# dxlboard.net
KiCad netlist of a schematic drawn in EAGLE
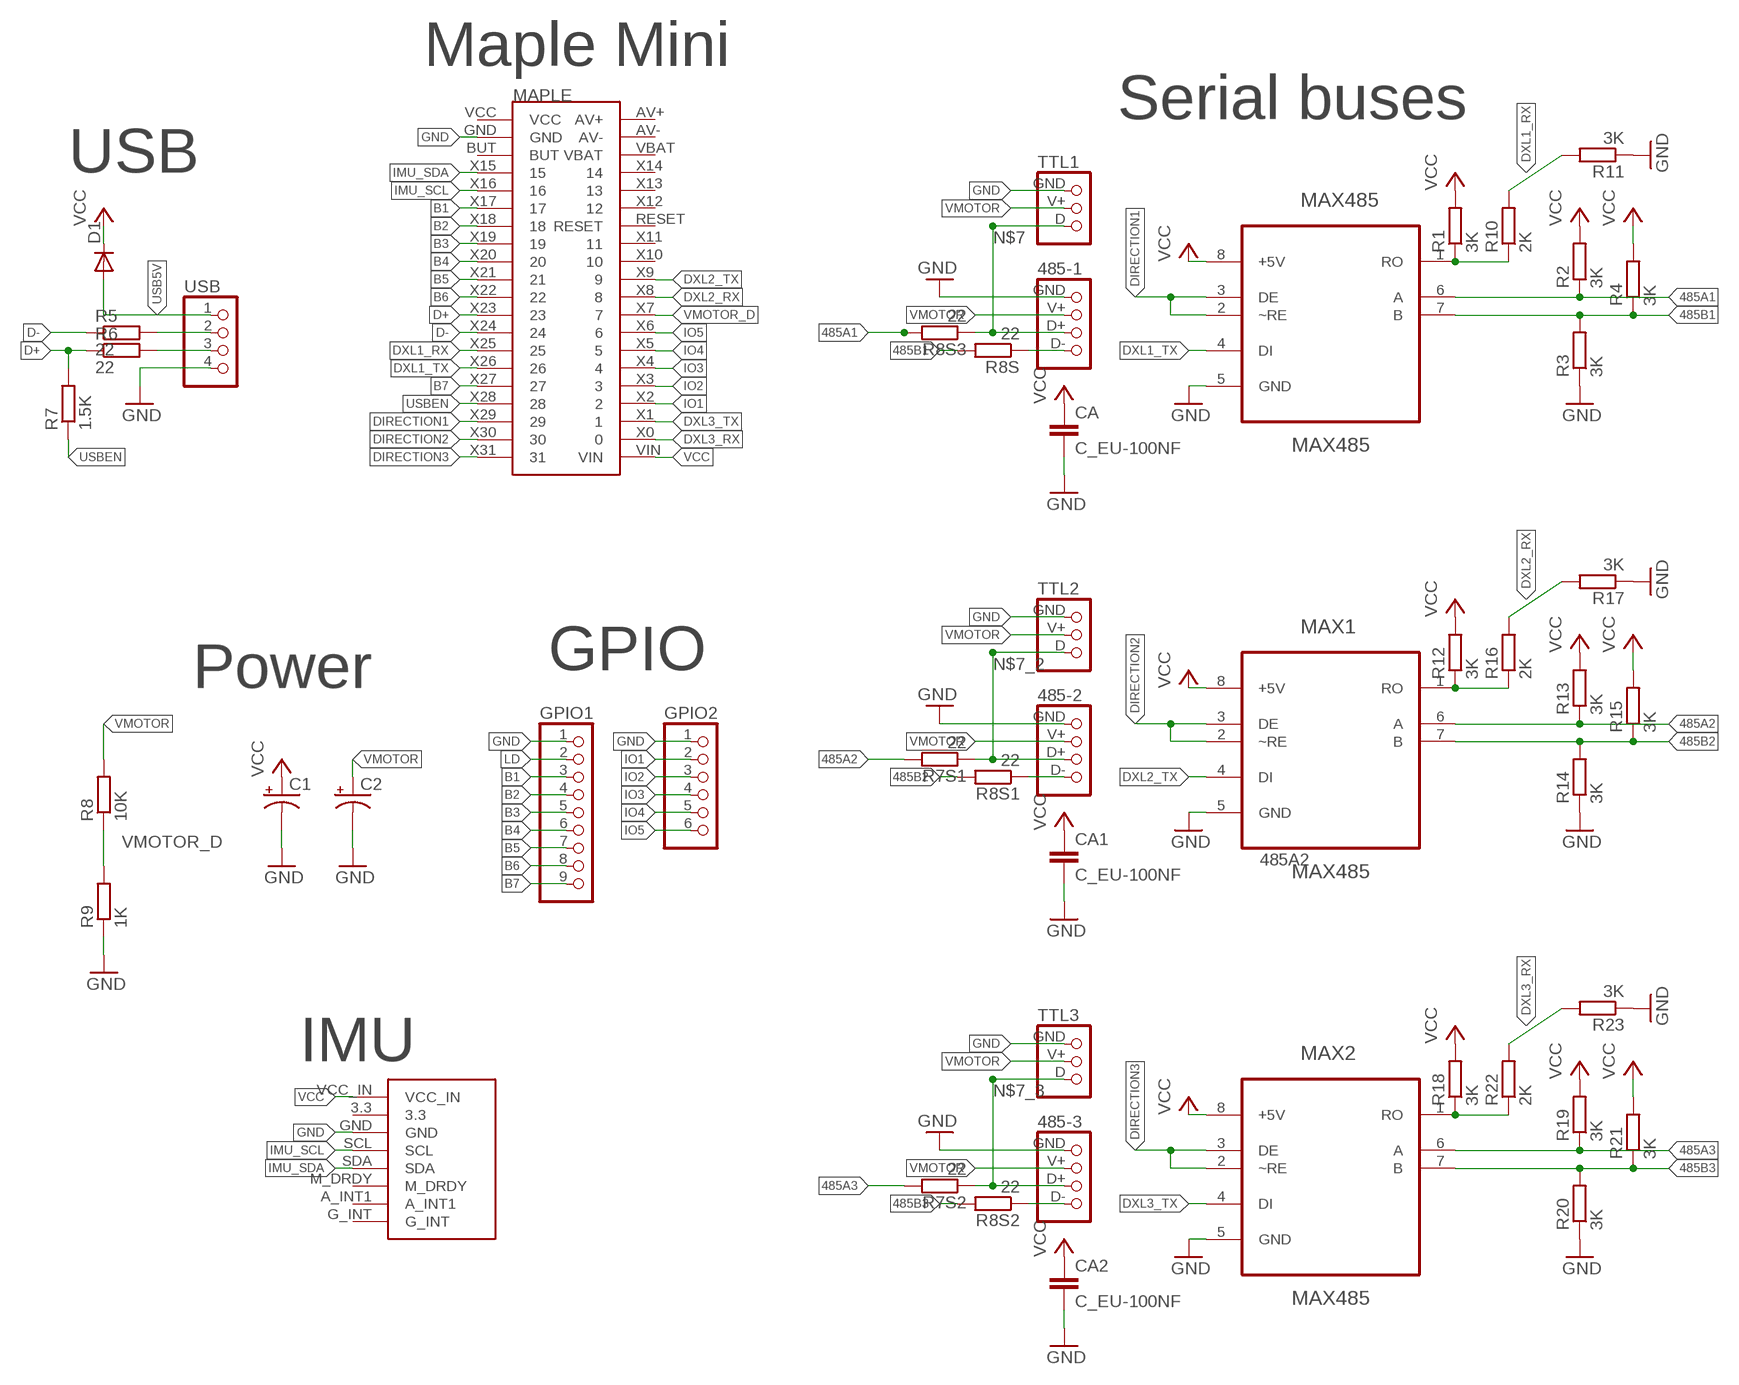
[diagram p0: schematic, sheet 1]

(export (version "E")
  (design (tool "Eeschema 10.0.6"))
  (components
    (comp (ref "485-1")
      (value "CONNEC_1X04_485")
      (footprint "eagle-import:CONNEC_485")
      (libsource (lib "eagle-import") (part "CONNEC_1X04_485"))
    )
    (comp (ref "485-2")
      (value "CONNEC_1X04_485")
      (footprint "eagle-import:CONNEC_485")
      (libsource (lib "eagle-import") (part "CONNEC_1X04_485"))
    )
    (comp (ref "485-3")
      (value "CONNEC_1X04_485")
      (footprint "eagle-import:CONNEC_485")
      (libsource (lib "eagle-import") (part "CONNEC_1X04_485"))
    )
    (comp (ref "C1")
      (value "CAP_POLPTH2")
      (footprint "eagle-import:CPOL-RADIAL-10UF-25V")
      (libsource (lib "eagle-import") (part "CAP_POLPTH2"))
    )
    (comp (ref "C2")
      (value "CAP_POLPTH2")
      (footprint "eagle-import:CPOL-RADIAL-10UF-25V")
      (libsource (lib "eagle-import") (part "CAP_POLPTH2"))
    )
    (comp (ref "CA")
      (value "C_EU-100NF")
      (footprint "eagle-import:C0805")
      (libsource (lib "eagle-import") (part "C_EU-100NF"))
    )
    (comp (ref "CA1")
      (value "C_EU-100NF")
      (footprint "eagle-import:C0805")
      (libsource (lib "eagle-import") (part "C_EU-100NF"))
    )
    (comp (ref "CA2")
      (value "C_EU-100NF")
      (footprint "eagle-import:C0805")
      (libsource (lib "eagle-import") (part "C_EU-100NF"))
    )
    (comp (ref "D1")
      (value "DIODESOD")
      (footprint "eagle-import:SOD-323")
      (libsource (lib "eagle-import") (part "DIODESOD"))
    )
    (comp (ref "GPIO1")
      (value "CONNEC_1X09")
      (footprint "eagle-import:CONNEC_1X09")
      (libsource (lib "eagle-import") (part "CONNEC_1X09"))
    )
    (comp (ref "GPIO2")
      (value "CONNEC_1X06")
      (footprint "eagle-import:CONNEC_1X06")
      (libsource (lib "eagle-import") (part "CONNEC_1X06"))
    )
    (comp (ref "MAPLE")
      (value "MAPLE_MINI")
      (footprint "eagle-import:CONNEC_2X20")
      (libsource (lib "eagle-import") (part "MAPLE_MINI"))
    )
    (comp (ref "MAX1")
      (value "MAX485")
      (footprint "eagle-import:SO8")
      (fields (field (name "MPN") "MAX485EESA+"))
      (libsource (lib "eagle-import") (part "MAX485"))
    )
    (comp (ref "MAX2")
      (value "MAX485")
      (footprint "eagle-import:SO8")
      (fields (field (name "MPN") "MAX485EESA+"))
      (libsource (lib "eagle-import") (part "MAX485"))
    )
    (comp (ref "MAX485")
      (value "MAX485")
      (footprint "eagle-import:SO8")
      (fields (field (name "MPN") "MAX485EESA+"))
      (libsource (lib "eagle-import") (part "MAX485"))
    )
    (comp (ref "R1")
      (value "3K")
      (footprint "eagle-import:R0805")
      (libsource (lib "eagle-import") (part "RESISTANCE-R0805"))
    )
    (comp (ref "R2")
      (value "3K")
      (footprint "eagle-import:R0805")
      (libsource (lib "eagle-import") (part "RESISTANCE-R0805"))
    )
    (comp (ref "R3")
      (value "3K")
      (footprint "eagle-import:R0805")
      (libsource (lib "eagle-import") (part "RESISTANCE-R0805"))
    )
    (comp (ref "R4")
      (value "3K")
      (footprint "eagle-import:R0805")
      (libsource (lib "eagle-import") (part "RESISTANCE-R0805"))
    )
    (comp (ref "R5")
      (value "22")
      (footprint "eagle-import:R0805")
      (libsource (lib "eagle-import") (part "RESISTANCE-R0805"))
    )
    (comp (ref "R6")
      (value "22")
      (footprint "eagle-import:R0805")
      (libsource (lib "eagle-import") (part "RESISTANCE-R0805"))
    )
    (comp (ref "R7")
      (value "1.5K")
      (footprint "eagle-import:R0805")
      (libsource (lib "eagle-import") (part "RESISTANCE-R0805"))
    )
    (comp (ref "R7S1")
      (value "22")
      (footprint "eagle-import:R0805")
      (libsource (lib "eagle-import") (part "RESISTANCE-R0805"))
    )
    (comp (ref "R7S2")
      (value "22")
      (footprint "eagle-import:R0805")
      (libsource (lib "eagle-import") (part "RESISTANCE-R0805"))
    )
    (comp (ref "R8")
      (value "10K")
      (footprint "eagle-import:R0805")
      (libsource (lib "eagle-import") (part "RESISTANCE-R0805"))
    )
    (comp (ref "R8S")
      (value "22")
      (footprint "eagle-import:R0805")
      (libsource (lib "eagle-import") (part "RESISTANCE-R0805"))
    )
    (comp (ref "R8S1")
      (value "22")
      (footprint "eagle-import:R0805")
      (libsource (lib "eagle-import") (part "RESISTANCE-R0805"))
    )
    (comp (ref "R8S2")
      (value "22")
      (footprint "eagle-import:R0805")
      (libsource (lib "eagle-import") (part "RESISTANCE-R0805"))
    )
    (comp (ref "R8S3")
      (value "22")
      (footprint "eagle-import:R0805")
      (libsource (lib "eagle-import") (part "RESISTANCE-R0805"))
    )
    (comp (ref "R9")
      (value "1K")
      (footprint "eagle-import:R0805")
      (libsource (lib "eagle-import") (part "RESISTANCE-R0805"))
    )
    (comp (ref "R10")
      (value "2K")
      (footprint "eagle-import:R0805")
      (libsource (lib "eagle-import") (part "RESISTANCE-R0805"))
    )
    (comp (ref "R11")
      (value "3K")
      (footprint "eagle-import:R0805")
      (libsource (lib "eagle-import") (part "RESISTANCE-R0805"))
    )
    (comp (ref "R12")
      (value "3K")
      (footprint "eagle-import:R0805")
      (libsource (lib "eagle-import") (part "RESISTANCE-R0805"))
    )
    (comp (ref "R13")
      (value "3K")
      (footprint "eagle-import:R0805")
      (libsource (lib "eagle-import") (part "RESISTANCE-R0805"))
    )
    (comp (ref "R14")
      (value "3K")
      (footprint "eagle-import:R0805")
      (libsource (lib "eagle-import") (part "RESISTANCE-R0805"))
    )
    (comp (ref "R15")
      (value "3K")
      (footprint "eagle-import:R0805")
      (libsource (lib "eagle-import") (part "RESISTANCE-R0805"))
    )
    (comp (ref "R16")
      (value "2K")
      (footprint "eagle-import:R0805")
      (libsource (lib "eagle-import") (part "RESISTANCE-R0805"))
    )
    (comp (ref "R17")
      (value "3K")
      (footprint "eagle-import:R0805")
      (libsource (lib "eagle-import") (part "RESISTANCE-R0805"))
    )
    (comp (ref "R18")
      (value "3K")
      (footprint "eagle-import:R0805")
      (libsource (lib "eagle-import") (part "RESISTANCE-R0805"))
    )
    (comp (ref "R19")
      (value "3K")
      (footprint "eagle-import:R0805")
      (libsource (lib "eagle-import") (part "RESISTANCE-R0805"))
    )
    (comp (ref "R20")
      (value "3K")
      (footprint "eagle-import:R0805")
      (libsource (lib "eagle-import") (part "RESISTANCE-R0805"))
    )
    (comp (ref "R21")
      (value "3K")
      (footprint "eagle-import:R0805")
      (libsource (lib "eagle-import") (part "RESISTANCE-R0805"))
    )
    (comp (ref "R22")
      (value "2K")
      (footprint "eagle-import:R0805")
      (libsource (lib "eagle-import") (part "RESISTANCE-R0805"))
    )
    (comp (ref "R23")
      (value "3K")
      (footprint "eagle-import:R0805")
      (libsource (lib "eagle-import") (part "RESISTANCE-R0805"))
    )
    (comp (ref "TTL1")
      (value "CONNEC_1X03_TTL")
      (footprint "eagle-import:CONNEC_TTL")
      (libsource (lib "eagle-import") (part "CONNEC_1X03_TTL"))
    )
    (comp (ref "TTL2")
      (value "CONNEC_1X03_TTL")
      (footprint "eagle-import:CONNEC_TTL")
      (libsource (lib "eagle-import") (part "CONNEC_1X03_TTL"))
    )
    (comp (ref "TTL3")
      (value "CONNEC_1X03_TTL")
      (footprint "eagle-import:CONNEC_TTL")
      (libsource (lib "eagle-import") (part "CONNEC_1X03_TTL"))
    )
    (comp (ref "U$6")
      (value "GY-85")
      (footprint "eagle-import:GY-85")
      (libsource (lib "eagle-import") (part "GY-85"))
    )
    (comp (ref "USB")
      (value "CONNEC_1X04")
      (footprint "eagle-import:CONNEC_1X04")
      (libsource (lib "eagle-import") (part "CONNEC_1X04"))
    )
  )
  (nets
    (net (code "1") (name "/N$7") (class "Default")
      (node (ref "485-1") (pin "D+") (pinfunction "3_D+") (pintype "passive"))
      (node (ref "R8S3") (pin "1") (pinfunction "1_1") (pintype "passive"))
      (node (ref "TTL1") (pin "D") (pinfunction "3_D") (pintype "passive"))
    )
    (net (code "2") (name "/N$7_2") (class "Default")
      (node (ref "485-2") (pin "D+") (pinfunction "3_D+") (pintype "passive"))
      (node (ref "R7S1") (pin "1") (pinfunction "1_1") (pintype "passive"))
      (node (ref "TTL2") (pin "D") (pinfunction "3_D") (pintype "passive"))
    )
    (net (code "3") (name "/N$7_3") (class "Default")
      (node (ref "485-3") (pin "D+") (pinfunction "3_D+") (pintype "passive"))
      (node (ref "R7S2") (pin "1") (pinfunction "1_1") (pintype "passive"))
      (node (ref "TTL3") (pin "D") (pinfunction "3_D") (pintype "passive"))
    )
    (net (code "4") (name "485A1") (class "Default")
      (node (ref "MAX485") (pin "6") (pinfunction "A_6") (pintype "bidirectional"))
      (node (ref "R2") (pin "1") (pinfunction "1_1") (pintype "passive"))
      (node (ref "R8S3") (pin "2") (pinfunction "2_2") (pintype "passive"))
    )
    (net (code "5") (name "485A2") (class "Default")
      (node (ref "MAX1") (pin "6") (pinfunction "A_6") (pintype "bidirectional"))
      (node (ref "R13") (pin "1") (pinfunction "1_1") (pintype "passive"))
      (node (ref "R7S1") (pin "2") (pinfunction "2_2") (pintype "passive"))
    )
    (net (code "6") (name "485A3") (class "Default")
      (node (ref "MAX2") (pin "6") (pinfunction "A_6") (pintype "bidirectional"))
      (node (ref "R19") (pin "1") (pinfunction "1_1") (pintype "passive"))
      (node (ref "R7S2") (pin "2") (pinfunction "2_2") (pintype "passive"))
    )
    (net (code "7") (name "485B1") (class "Default")
      (node (ref "MAX485") (pin "7") (pinfunction "B_7") (pintype "bidirectional"))
      (node (ref "R3") (pin "2") (pinfunction "2_2") (pintype "passive"))
      (node (ref "R4") (pin "1") (pinfunction "1_1") (pintype "passive"))
      (node (ref "R8S") (pin "2") (pinfunction "2_2") (pintype "passive"))
    )
    (net (code "8") (name "485B2") (class "Default")
      (node (ref "MAX1") (pin "7") (pinfunction "B_7") (pintype "bidirectional"))
      (node (ref "R14") (pin "2") (pinfunction "2_2") (pintype "passive"))
      (node (ref "R15") (pin "1") (pinfunction "1_1") (pintype "passive"))
      (node (ref "R8S1") (pin "2") (pinfunction "2_2") (pintype "passive"))
    )
    (net (code "9") (name "485B3") (class "Default")
      (node (ref "MAX2") (pin "7") (pinfunction "B_7") (pintype "bidirectional"))
      (node (ref "R20") (pin "2") (pinfunction "2_2") (pintype "passive"))
      (node (ref "R21") (pin "1") (pinfunction "1_1") (pintype "passive"))
      (node (ref "R8S2") (pin "2") (pinfunction "2_2") (pintype "passive"))
    )
    (net (code "10") (name "B1") (class "Default")
      (node (ref "GPIO1") (pin "3") (pinfunction "3_3") (pintype "passive"))
      (node (ref "MAPLE") (pin "X17") (pinfunction "17_X17") (pintype "bidirectional"))
    )
    (net (code "11") (name "B2") (class "Default")
      (node (ref "GPIO1") (pin "4") (pinfunction "4_4") (pintype "passive"))
      (node (ref "MAPLE") (pin "X18") (pinfunction "18_X18") (pintype "bidirectional"))
    )
    (net (code "12") (name "B3") (class "Default")
      (node (ref "GPIO1") (pin "5") (pinfunction "5_5") (pintype "passive"))
      (node (ref "MAPLE") (pin "X19") (pinfunction "19_X19") (pintype "bidirectional"))
    )
    (net (code "13") (name "B4") (class "Default")
      (node (ref "GPIO1") (pin "6") (pinfunction "6_6") (pintype "passive"))
      (node (ref "MAPLE") (pin "X20") (pinfunction "20_X20") (pintype "bidirectional"))
    )
    (net (code "14") (name "B5") (class "Default")
      (node (ref "GPIO1") (pin "7") (pinfunction "7_7") (pintype "passive"))
      (node (ref "MAPLE") (pin "X21") (pinfunction "21_X21") (pintype "bidirectional"))
    )
    (net (code "15") (name "B6") (class "Default")
      (node (ref "GPIO1") (pin "8") (pinfunction "8_8") (pintype "passive"))
      (node (ref "MAPLE") (pin "X22") (pinfunction "22_X22") (pintype "bidirectional"))
    )
    (net (code "16") (name "B7") (class "Default")
      (node (ref "GPIO1") (pin "9") (pinfunction "9_9") (pintype "passive"))
      (node (ref "MAPLE") (pin "X27") (pinfunction "27_X27") (pintype "bidirectional"))
    )
    (net (code "17") (name "D+") (class "Default")
      (node (ref "MAPLE") (pin "X23") (pinfunction "23_X23") (pintype "bidirectional"))
      (node (ref "R6") (pin "1") (pinfunction "1_1") (pintype "passive"))
      (node (ref "R7") (pin "2") (pinfunction "2_2") (pintype "passive"))
    )
    (net (code "18") (name "D-") (class "Default")
      (node (ref "MAPLE") (pin "X24") (pinfunction "24_X24") (pintype "bidirectional"))
      (node (ref "R5") (pin "1") (pinfunction "1_1") (pintype "passive"))
    )
    (net (code "19") (name "DIRECTION1") (class "Default")
      (node (ref "MAPLE") (pin "X29") (pinfunction "29_X29") (pintype "bidirectional"))
      (node (ref "MAX485") (pin "2") (pinfunction "~{RE}_2") (pintype "input"))
      (node (ref "MAX485") (pin "3") (pinfunction "DE_3") (pintype "input"))
    )
    (net (code "20") (name "DIRECTION2") (class "Default")
      (node (ref "MAPLE") (pin "X30") (pinfunction "30_X30") (pintype "bidirectional"))
      (node (ref "MAX1") (pin "2") (pinfunction "~{RE}_2") (pintype "input"))
      (node (ref "MAX1") (pin "3") (pinfunction "DE_3") (pintype "input"))
    )
    (net (code "21") (name "DIRECTION3") (class "Default")
      (node (ref "MAPLE") (pin "X31") (pinfunction "31_X31") (pintype "bidirectional"))
      (node (ref "MAX2") (pin "2") (pinfunction "~{RE}_2") (pintype "input"))
      (node (ref "MAX2") (pin "3") (pinfunction "DE_3") (pintype "input"))
    )
    (net (code "22") (name "DXL1_RX") (class "Default")
      (node (ref "MAPLE") (pin "X25") (pinfunction "25_X25") (pintype "bidirectional"))
      (node (ref "R10") (pin "2") (pinfunction "2_2") (pintype "passive"))
      (node (ref "R11") (pin "2") (pinfunction "2_2") (pintype "passive"))
    )
    (net (code "23") (name "DXL1_TX") (class "Default")
      (node (ref "MAPLE") (pin "X26") (pinfunction "26_X26") (pintype "bidirectional"))
      (node (ref "MAX485") (pin "4") (pinfunction "DI_4") (pintype "input"))
    )
    (net (code "24") (name "DXL2_RX") (class "Default")
      (node (ref "MAPLE") (pin "X8") (pinfunction "8_X8") (pintype "bidirectional"))
      (node (ref "R16") (pin "2") (pinfunction "2_2") (pintype "passive"))
      (node (ref "R17") (pin "2") (pinfunction "2_2") (pintype "passive"))
    )
    (net (code "25") (name "DXL2_TX") (class "Default")
      (node (ref "MAPLE") (pin "X9") (pinfunction "9_X9") (pintype "bidirectional"))
      (node (ref "MAX1") (pin "4") (pinfunction "DI_4") (pintype "input"))
    )
    (net (code "26") (name "DXL3_RX") (class "Default")
      (node (ref "MAPLE") (pin "X0") (pinfunction "0_X0") (pintype "bidirectional"))
      (node (ref "R22") (pin "2") (pinfunction "2_2") (pintype "passive"))
      (node (ref "R23") (pin "2") (pinfunction "2_2") (pintype "passive"))
    )
    (net (code "27") (name "DXL3_TX") (class "Default")
      (node (ref "MAPLE") (pin "X1") (pinfunction "1_X1") (pintype "bidirectional"))
      (node (ref "MAX2") (pin "4") (pinfunction "DI_4") (pintype "input"))
    )
    (net (code "28") (name "GND") (class "Default")
      (node (ref "485-1") (pin "GND") (pinfunction "1_GND") (pintype "passive"))
      (node (ref "485-2") (pin "GND") (pinfunction "1_GND") (pintype "passive"))
      (node (ref "485-3") (pin "GND") (pinfunction "1_GND") (pintype "passive"))
      (node (ref "C1") (pin "2") (pinfunction "-_2") (pintype "passive"))
      (node (ref "C2") (pin "2") (pinfunction "-_2") (pintype "passive"))
      (node (ref "CA") (pin "2") (pinfunction "2_2") (pintype "passive"))
      (node (ref "CA1") (pin "2") (pinfunction "2_2") (pintype "passive"))
      (node (ref "CA2") (pin "2") (pinfunction "2_2") (pintype "passive"))
      (node (ref "GPIO1") (pin "1") (pinfunction "1_1") (pintype "passive"))
      (node (ref "GPIO2") (pin "1") (pinfunction "1_1") (pintype "passive"))
      (node (ref "MAPLE") (pin "GND") (pinfunction "GND_GND") (pintype "bidirectional"))
      (node (ref "MAX1") (pin "5") (pinfunction "GND_5") (pintype "passive"))
      (node (ref "MAX2") (pin "5") (pinfunction "GND_5") (pintype "passive"))
      (node (ref "MAX485") (pin "5") (pinfunction "GND_5") (pintype "passive"))
      (node (ref "R11") (pin "1") (pinfunction "1_1") (pintype "passive"))
      (node (ref "R14") (pin "1") (pinfunction "1_1") (pintype "passive"))
      (node (ref "R17") (pin "1") (pinfunction "1_1") (pintype "passive"))
      (node (ref "R20") (pin "1") (pinfunction "1_1") (pintype "passive"))
      (node (ref "R23") (pin "1") (pinfunction "1_1") (pintype "passive"))
      (node (ref "R3") (pin "1") (pinfunction "1_1") (pintype "passive"))
      (node (ref "R9") (pin "1") (pinfunction "1_1") (pintype "passive"))
      (node (ref "TTL1") (pin "GND") (pinfunction "1_GND") (pintype "passive"))
      (node (ref "TTL2") (pin "GND") (pinfunction "1_GND") (pintype "passive"))
      (node (ref "TTL3") (pin "GND") (pinfunction "1_GND") (pintype "passive"))
      (node (ref "U$6") (pin "GND") (pinfunction "GND_GND") (pintype "bidirectional"))
      (node (ref "USB") (pin "4") (pinfunction "4_4") (pintype "passive"))
    )
    (net (code "29") (name "IMU_SCL") (class "Default")
      (node (ref "MAPLE") (pin "X16") (pinfunction "16_X16") (pintype "bidirectional"))
      (node (ref "U$6") (pin "SCL") (pinfunction "SCL_SCL") (pintype "bidirectional"))
    )
    (net (code "30") (name "IMU_SDA") (class "Default")
      (node (ref "MAPLE") (pin "X15") (pinfunction "15_X15") (pintype "bidirectional"))
      (node (ref "U$6") (pin "SDA") (pinfunction "SDA_SDA") (pintype "bidirectional"))
    )
    (net (code "31") (name "IO1") (class "Default")
      (node (ref "GPIO2") (pin "2") (pinfunction "2_2") (pintype "passive"))
      (node (ref "MAPLE") (pin "X2") (pinfunction "2_X2") (pintype "bidirectional"))
    )
    (net (code "32") (name "IO2") (class "Default")
      (node (ref "GPIO2") (pin "3") (pinfunction "3_3") (pintype "passive"))
      (node (ref "MAPLE") (pin "X3") (pinfunction "3_X3") (pintype "bidirectional"))
    )
    (net (code "33") (name "IO3") (class "Default")
      (node (ref "GPIO2") (pin "4") (pinfunction "4_4") (pintype "passive"))
      (node (ref "MAPLE") (pin "X4") (pinfunction "4_X4") (pintype "bidirectional"))
    )
    (net (code "34") (name "IO4") (class "Default")
      (node (ref "GPIO2") (pin "5") (pinfunction "5_5") (pintype "passive"))
      (node (ref "MAPLE") (pin "X5") (pinfunction "5_X5") (pintype "bidirectional"))
    )
    (net (code "35") (name "IO5") (class "Default")
      (node (ref "GPIO2") (pin "6") (pinfunction "6_6") (pintype "passive"))
      (node (ref "MAPLE") (pin "X6") (pinfunction "6_X6") (pintype "bidirectional"))
    )
    (net (code "36") (name "LD") (class "Default")
      (node (ref "GPIO1") (pin "2") (pinfunction "2_2") (pintype "passive"))
    )
    (net (code "37") (name "Net-(485-1-4)") (class "Default")
      (node (ref "485-1") (pin "D-") (pinfunction "4_D-") (pintype "passive"))
      (node (ref "R8S") (pin "1") (pinfunction "1_1") (pintype "passive"))
    )
    (net (code "38") (name "Net-(485-2-4)") (class "Default")
      (node (ref "485-2") (pin "D-") (pinfunction "4_D-") (pintype "passive"))
      (node (ref "R8S1") (pin "1") (pinfunction "1_1") (pintype "passive"))
    )
    (net (code "39") (name "Net-(485-3-4)") (class "Default")
      (node (ref "485-3") (pin "D-") (pinfunction "4_D-") (pintype "passive"))
      (node (ref "R8S2") (pin "1") (pinfunction "1_1") (pintype "passive"))
    )
    (net (code "40") (name "Net-(MAX1-RO)") (class "Default")
      (node (ref "MAX1") (pin "1") (pinfunction "RO_1") (pintype "output"))
      (node (ref "R12") (pin "1") (pinfunction "1_1") (pintype "passive"))
      (node (ref "R16") (pin "1") (pinfunction "1_1") (pintype "passive"))
    )
    (net (code "41") (name "Net-(MAX2-RO)") (class "Default")
      (node (ref "MAX2") (pin "1") (pinfunction "RO_1") (pintype "output"))
      (node (ref "R18") (pin "1") (pinfunction "1_1") (pintype "passive"))
      (node (ref "R22") (pin "1") (pinfunction "1_1") (pintype "passive"))
    )
    (net (code "42") (name "Net-(MAX485-RO)") (class "Default")
      (node (ref "MAX485") (pin "1") (pinfunction "RO_1") (pintype "output"))
      (node (ref "R1") (pin "1") (pinfunction "1_1") (pintype "passive"))
      (node (ref "R10") (pin "1") (pinfunction "1_1") (pintype "passive"))
    )
    (net (code "43") (name "Net-(R5-Pad2)") (class "Default")
      (node (ref "R5") (pin "2") (pinfunction "2_2") (pintype "passive"))
      (node (ref "USB") (pin "2") (pinfunction "2_2") (pintype "passive"))
    )
    (net (code "44") (name "Net-(R6-Pad2)") (class "Default")
      (node (ref "R6") (pin "2") (pinfunction "2_2") (pintype "passive"))
      (node (ref "USB") (pin "3") (pinfunction "3_3") (pintype "passive"))
    )
    (net (code "45") (name "USB5V") (class "Default")
      (node (ref "D1") (pin "2") (pinfunction "A_2") (pintype "passive"))
      (node (ref "USB") (pin "1") (pinfunction "1_1") (pintype "passive"))
    )
    (net (code "46") (name "USBEN") (class "Default")
      (node (ref "MAPLE") (pin "X28") (pinfunction "28_X28") (pintype "bidirectional"))
      (node (ref "R7") (pin "1") (pinfunction "1_1") (pintype "passive"))
    )
    (net (code "47") (name "VCC") (class "Default")
      (node (ref "C1") (pin "1") (pinfunction "+_1") (pintype "passive"))
      (node (ref "CA") (pin "1") (pinfunction "1_1") (pintype "passive"))
      (node (ref "CA1") (pin "1") (pinfunction "1_1") (pintype "passive"))
      (node (ref "CA2") (pin "1") (pinfunction "1_1") (pintype "passive"))
      (node (ref "D1") (pin "1") (pinfunction "C_1") (pintype "passive"))
      (node (ref "MAPLE") (pin "VIN") (pinfunction "VIN_VIN") (pintype "bidirectional"))
      (node (ref "MAX1") (pin "8") (pinfunction "+5V_8") (pintype "power_in"))
      (node (ref "MAX2") (pin "8") (pinfunction "+5V_8") (pintype "power_in"))
      (node (ref "MAX485") (pin "8") (pinfunction "+5V_8") (pintype "power_in"))
      (node (ref "R1") (pin "2") (pinfunction "2_2") (pintype "passive"))
      (node (ref "R12") (pin "2") (pinfunction "2_2") (pintype "passive"))
      (node (ref "R13") (pin "2") (pinfunction "2_2") (pintype "passive"))
      (node (ref "R15") (pin "2") (pinfunction "2_2") (pintype "passive"))
      (node (ref "R18") (pin "2") (pinfunction "2_2") (pintype "passive"))
      (node (ref "R19") (pin "2") (pinfunction "2_2") (pintype "passive"))
      (node (ref "R2") (pin "2") (pinfunction "2_2") (pintype "passive"))
      (node (ref "R21") (pin "2") (pinfunction "2_2") (pintype "passive"))
      (node (ref "R4") (pin "2") (pinfunction "2_2") (pintype "passive"))
      (node (ref "U$6") (pin "VCC_IN") (pinfunction "VCC_IN_VCC_IN") (pintype "bidirectional"))
    )
    (net (code "48") (name "VMOTOR") (class "Default")
      (node (ref "485-1") (pin "V+") (pinfunction "2_V+") (pintype "passive"))
      (node (ref "485-2") (pin "V+") (pinfunction "2_V+") (pintype "passive"))
      (node (ref "485-3") (pin "V+") (pinfunction "2_V+") (pintype "passive"))
      (node (ref "C2") (pin "1") (pinfunction "+_1") (pintype "passive"))
      (node (ref "R8") (pin "2") (pinfunction "2_2") (pintype "passive"))
      (node (ref "TTL1") (pin "V+") (pinfunction "2_V+") (pintype "passive"))
      (node (ref "TTL2") (pin "V+") (pinfunction "2_V+") (pintype "passive"))
      (node (ref "TTL3") (pin "V+") (pinfunction "2_V+") (pintype "passive"))
    )
    (net (code "49") (name "VMOTOR_D") (class "Default")
      (node (ref "MAPLE") (pin "X7") (pinfunction "7_X7") (pintype "bidirectional"))
      (node (ref "R8") (pin "1") (pinfunction "1_1") (pintype "passive"))
      (node (ref "R9") (pin "2") (pinfunction "2_2") (pintype "passive"))
    )
    (net (code "50") (name "unconnected-(MAPLE-10-PadX10)") (class "Default")
      (node (ref "MAPLE") (pin "X10") (pinfunction "10_X10") (pintype "bidirectional"))
    )
    (net (code "51") (name "unconnected-(MAPLE-11-PadX11)") (class "Default")
      (node (ref "MAPLE") (pin "X11") (pinfunction "11_X11") (pintype "bidirectional"))
    )
    (net (code "52") (name "unconnected-(MAPLE-12-PadX12)") (class "Default")
      (node (ref "MAPLE") (pin "X12") (pinfunction "12_X12") (pintype "bidirectional"))
    )
    (net (code "53") (name "unconnected-(MAPLE-13-PadX13)") (class "Default")
      (node (ref "MAPLE") (pin "X13") (pinfunction "13_X13") (pintype "bidirectional"))
    )
    (net (code "54") (name "unconnected-(MAPLE-14-PadX14)") (class "Default")
      (node (ref "MAPLE") (pin "X14") (pinfunction "14_X14") (pintype "bidirectional"))
    )
    (net (code "55") (name "unconnected-(MAPLE-PadAV+)") (class "Default")
      (node (ref "MAPLE") (pin "AV+") (pinfunction "AV+_AV+") (pintype "bidirectional"))
    )
    (net (code "56") (name "unconnected-(MAPLE-PadAV-)") (class "Default")
      (node (ref "MAPLE") (pin "AV-") (pinfunction "AV-_AV-") (pintype "bidirectional"))
    )
    (net (code "57") (name "unconnected-(MAPLE-PadBUT)") (class "Default")
      (node (ref "MAPLE") (pin "BUT") (pinfunction "BUT_BUT") (pintype "bidirectional"))
    )
    (net (code "58") (name "unconnected-(MAPLE-PadRESET)") (class "Default")
      (node (ref "MAPLE") (pin "RESET") (pinfunction "RESET_RESET") (pintype "bidirectional"))
    )
    (net (code "59") (name "unconnected-(MAPLE-PadVBAT)") (class "Default")
      (node (ref "MAPLE") (pin "VBAT") (pinfunction "VBAT_VBAT") (pintype "bidirectional"))
    )
    (net (code "60") (name "unconnected-(MAPLE-PadVCC)") (class "Default")
      (node (ref "MAPLE") (pin "VCC") (pinfunction "VCC_VCC") (pintype "bidirectional"))
    )
    (net (code "61") (name "unconnected-(U$6-Pad3.3)") (class "Default")
      (node (ref "U$6") (pin "3.3") (pinfunction "3.3_3.3") (pintype "bidirectional"))
    )
    (net (code "62") (name "unconnected-(U$6-PadA_INT1)") (class "Default")
      (node (ref "U$6") (pin "A_INT1") (pinfunction "A_INT1_A_INT1") (pintype "bidirectional"))
    )
    (net (code "63") (name "unconnected-(U$6-PadG_INT)") (class "Default")
      (node (ref "U$6") (pin "G_INT") (pinfunction "G_INT_G_INT") (pintype "bidirectional"))
    )
    (net (code "64") (name "unconnected-(U$6-PadM_DRDY)") (class "Default")
      (node (ref "U$6") (pin "M_DRDY") (pinfunction "M_DRDY_M_DRDY") (pintype "bidirectional"))
    )
  )
)
